# EEG_interface.net
KiCad netlist of a schematic drawn in EAGLE
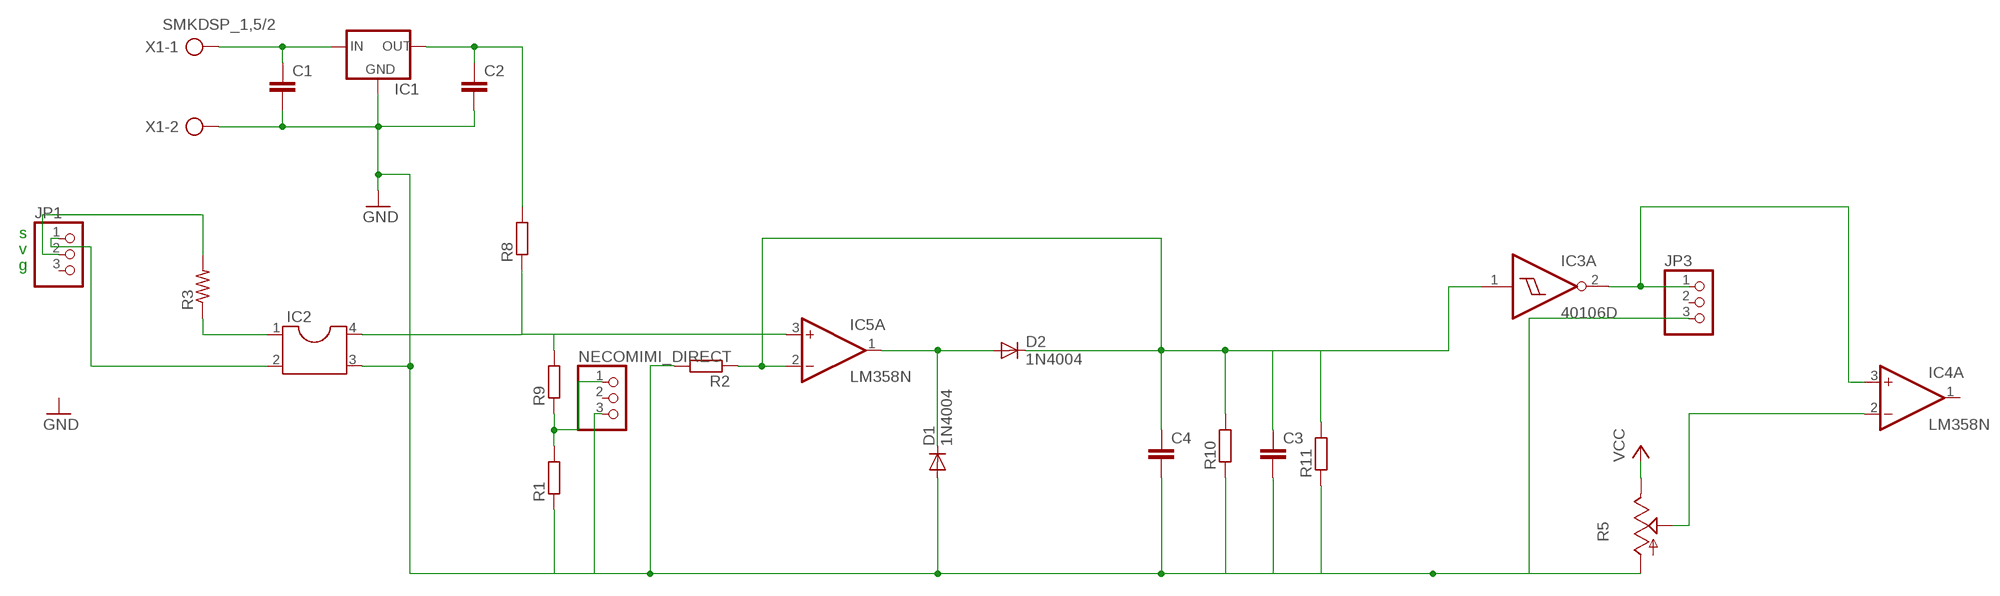
[diagram p0: schematic, sheet 1]

(export (version "E")
  (design (tool "Eeschema 10.0.6"))
  (components
    (comp (ref "C1")
      (value "C2,5-3")
      (footprint "eagle-import:C2.5-3")
      (libsource (lib "eagle-import") (part "C2,5-3"))
    )
    (comp (ref "C2")
      (value "C2,5-3")
      (footprint "eagle-import:C2.5-3")
      (libsource (lib "eagle-import") (part "C2,5-3"))
    )
    (comp (ref "C3")
      (value "C2,5-3")
      (footprint "eagle-import:C2.5-3")
      (libsource (lib "eagle-import") (part "C2,5-3"))
    )
    (comp (ref "C4")
      (value "C2,5-3")
      (footprint "eagle-import:C2.5-3")
      (libsource (lib "eagle-import") (part "C2,5-3"))
    )
    (comp (ref "D1")
      (value "1N4004")
      (footprint "eagle-import:DO41-10")
      (libsource (lib "eagle-import") (part "1N4004"))
    )
    (comp (ref "D2")
      (value "1N4004")
      (footprint "eagle-import:DO41-10")
      (libsource (lib "eagle-import") (part "1N4004"))
    )
    (comp (ref "IC1")
      (value "78XXS")
      (footprint "eagle-import:78XXS")
      (libsource (lib "eagle-import") (part "78XXS"))
    )
    (comp (ref "IC2")
      (value "DIL4")
      (footprint "eagle-import:DIL04")
      (libsource (lib "eagle-import") (part "DIL4"))
    )
    (comp (ref "IC3")
      (value "40106D")
      (footprint "eagle-import:SO14")
      (libsource (lib "eagle-import") (part "40106D"))
    )
    (comp (ref "IC4")
      (value "LM358N")
      (footprint "eagle-import:DIL08")
      (libsource (lib "eagle-import") (part "LM358N"))
    )
    (comp (ref "IC5")
      (value "LM358N")
      (footprint "eagle-import:DIL08")
      (libsource (lib "eagle-import") (part "LM358N"))
    )
    (comp (ref "JP1")
      (value "PINHD-1X3")
      (footprint "eagle-import:1X03")
      (libsource (lib "eagle-import") (part "PINHD-1X3"))
    )
    (comp (ref "JP3")
      (value "PINHD-1X3")
      (footprint "eagle-import:1X03")
      (libsource (lib "eagle-import") (part "PINHD-1X3"))
    )
    (comp (ref "NECOMIMI_DIRECT")
      (value "PINHD-1X3")
      (footprint "eagle-import:1X03")
      (libsource (lib "eagle-import") (part "PINHD-1X3"))
    )
    (comp (ref "R1")
      (value "R-EU_0207/12")
      (footprint "eagle-import:0207_12")
      (libsource (lib "eagle-import") (part "R-EU_0207/12"))
    )
    (comp (ref "R2")
      (value "R-EU_0207/12")
      (footprint "eagle-import:0207_12")
      (libsource (lib "eagle-import") (part "R-EU_0207/12"))
    )
    (comp (ref "R3")
      (value "R-US_0204/2V")
      (footprint "eagle-import:0204V")
      (libsource (lib "eagle-import") (part "R-US_0204/2V"))
    )
    (comp (ref "R5")
      (value "TRIM_US-3223G")
      (footprint "eagle-import:3223G")
      (libsource (lib "eagle-import") (part "TRIM_US-3223G"))
    )
    (comp (ref "R8")
      (value "R-EU_0207/12")
      (footprint "eagle-import:0207_12")
      (libsource (lib "eagle-import") (part "R-EU_0207/12"))
    )
    (comp (ref "R9")
      (value "R-EU_0207/12")
      (footprint "eagle-import:0207_12")
      (libsource (lib "eagle-import") (part "R-EU_0207/12"))
    )
    (comp (ref "R10")
      (value "R-EU_0207/12")
      (footprint "eagle-import:0207_12")
      (libsource (lib "eagle-import") (part "R-EU_0207/12"))
    )
    (comp (ref "R11")
      (value "R-EU_0207/12")
      (footprint "eagle-import:0207_12")
      (libsource (lib "eagle-import") (part "R-EU_0207/12"))
    )
    (comp (ref "X1")
      (value "SMKDSP_1,5/2")
      (footprint "eagle-import:SMKDSP_1,5_2")
      (fields (field (name "MF") "FARNELL") (field (name "MPN") "1733570"))
      (libsource (lib "eagle-import") (part "SMKDSP_1,5/2"))
    )
  )
  (nets
    (net (code "1") (name "GND") (class "Default")
      (node (ref "C1") (pin "2") (pinfunction "2_2") (pintype "passive"))
      (node (ref "C2") (pin "2") (pinfunction "2_2") (pintype "passive"))
      (node (ref "C3") (pin "2") (pinfunction "2_2") (pintype "passive"))
      (node (ref "C4") (pin "2") (pinfunction "2_2") (pintype "passive"))
      (node (ref "D1") (pin "A") (pinfunction "A_A") (pintype "passive"))
      (node (ref "IC1") (pin "GND") (pinfunction "GND_GND") (pintype "input"))
      (node (ref "IC2") (pin "3") (pinfunction "3_3") (pintype "passive"))
      (node (ref "JP3") (pin "3") (pinfunction "3_3") (pintype "passive"))
      (node (ref "NECOMIMI_DIRECT") (pin "3") (pinfunction "3_3") (pintype "passive"))
      (node (ref "R1") (pin "1") (pinfunction "1_1") (pintype "passive"))
      (node (ref "R10") (pin "1") (pinfunction "1_1") (pintype "passive"))
      (node (ref "R11") (pin "1") (pinfunction "1_1") (pintype "passive"))
      (node (ref "R2") (pin "2") (pinfunction "2_2") (pintype "passive"))
      (node (ref "R5") (pin "1") (pinfunction "A_1") (pintype "passive"))
      (node (ref "X1") (pin "2") (pinfunction "KL_2") (pintype "passive"))
    )
    (net (code "2") (name "Net-(C2-Pad1)") (class "Default")
      (node (ref "C2") (pin "1") (pinfunction "1_1") (pintype "passive"))
      (node (ref "IC1") (pin "OUT") (pinfunction "OUT_OUT") (pintype "passive"))
      (node (ref "R8") (pin "2") (pinfunction "2_2") (pintype "passive"))
    )
    (net (code "3") (name "Net-(IC2-Pad1)") (class "Default")
      (node (ref "IC2") (pin "1") (pinfunction "1_1") (pintype "passive"))
      (node (ref "R3") (pin "1") (pinfunction "1_1") (pintype "passive"))
    )
    (net (code "4") (name "Net-(IC2-Pad2)") (class "Default")
      (node (ref "IC2") (pin "2") (pinfunction "2_2") (pintype "passive"))
      (node (ref "JP1") (pin "1") (pinfunction "1_1") (pintype "passive"))
    )
    (net (code "5") (name "Net-(IC3A-I)") (class "Default")
      (node (ref "C3") (pin "1") (pinfunction "1_1") (pintype "passive"))
      (node (ref "C4") (pin "1") (pinfunction "1_1") (pintype "passive"))
      (node (ref "D2") (pin "C") (pinfunction "C_C") (pintype "passive"))
      (node (ref "IC3") (pin "1") (pinfunction "I_1") (pintype "input"))
      (node (ref "IC5") (pin "2") (pinfunction "-IN_2") (pintype "input"))
      (node (ref "R10") (pin "2") (pinfunction "2_2") (pintype "passive"))
      (node (ref "R11") (pin "2") (pinfunction "2_2") (pintype "passive"))
      (node (ref "R2") (pin "1") (pinfunction "1_1") (pintype "passive"))
    )
    (net (code "6") (name "Net-(IC3A-O)") (class "Default")
      (node (ref "IC3") (pin "2") (pinfunction "O_2") (pintype "output"))
      (node (ref "IC4") (pin "3") (pinfunction "+IN_3") (pintype "input"))
      (node (ref "JP3") (pin "1") (pinfunction "1_1") (pintype "passive"))
    )
    (net (code "7") (name "Net-(IC4A--IN)") (class "Default")
      (node (ref "IC4") (pin "2") (pinfunction "-IN_2") (pintype "input"))
      (node (ref "R5") (pin "2") (pinfunction "S_2") (pintype "passive"))
    )
    (net (code "8") (name "Net-(IC5A-+IN)") (class "Default")
      (node (ref "IC2") (pin "4") (pinfunction "4_4") (pintype "passive"))
      (node (ref "IC5") (pin "3") (pinfunction "+IN_3") (pintype "input"))
      (node (ref "R8") (pin "1") (pinfunction "1_1") (pintype "passive"))
      (node (ref "R9") (pin "2") (pinfunction "2_2") (pintype "passive"))
    )
    (net (code "9") (name "Net-(IC5A-OUT)") (class "Default")
      (node (ref "D1") (pin "C") (pinfunction "C_C") (pintype "passive"))
      (node (ref "D2") (pin "A") (pinfunction "A_A") (pintype "passive"))
      (node (ref "IC5") (pin "1") (pinfunction "OUT_1") (pintype "output"))
    )
    (net (code "10") (name "Net-(JP1-Pad2)") (class "Default")
      (node (ref "JP1") (pin "2") (pinfunction "2_2") (pintype "passive"))
      (node (ref "R3") (pin "2") (pinfunction "2_2") (pintype "passive"))
    )
    (net (code "11") (name "Net-(NECOMIMI_DIRECT-Pad1)") (class "Default")
      (node (ref "NECOMIMI_DIRECT") (pin "1") (pinfunction "1_1") (pintype "passive"))
      (node (ref "R1") (pin "2") (pinfunction "2_2") (pintype "passive"))
      (node (ref "R9") (pin "1") (pinfunction "1_1") (pintype "passive"))
    )
    (net (code "12") (name "Net-(X1A-KL)") (class "Default")
      (node (ref "C1") (pin "1") (pinfunction "1_1") (pintype "passive"))
      (node (ref "IC1") (pin "IN") (pinfunction "IN_IN") (pintype "input"))
      (node (ref "X1") (pin "1") (pinfunction "KL_1") (pintype "passive"))
    )
    (net (code "13") (name "VCC") (class "Default")
      (node (ref "R5") (pin "3") (pinfunction "E_3") (pintype "passive"))
    )
    (net (code "14") (name "unconnected-(IC4A-OUT-Pad1)") (class "Default")
      (node (ref "IC4") (pin "1") (pinfunction "OUT_1") (pintype "output"))
    )
    (net (code "15") (name "unconnected-(JP1-Pad3)") (class "Default")
      (node (ref "JP1") (pin "3") (pinfunction "3_3") (pintype "passive"))
    )
    (net (code "16") (name "unconnected-(JP3-Pad2)") (class "Default")
      (node (ref "JP3") (pin "2") (pinfunction "2_2") (pintype "passive"))
    )
    (net (code "17") (name "unconnected-(NECOMIMI_DIRECT-Pad2)") (class "Default")
      (node (ref "NECOMIMI_DIRECT") (pin "2") (pinfunction "2_2") (pintype "passive"))
    )
  )
)
